# 4-20mA-generator.net
KiCad netlist of a schematic drawn in EAGLE
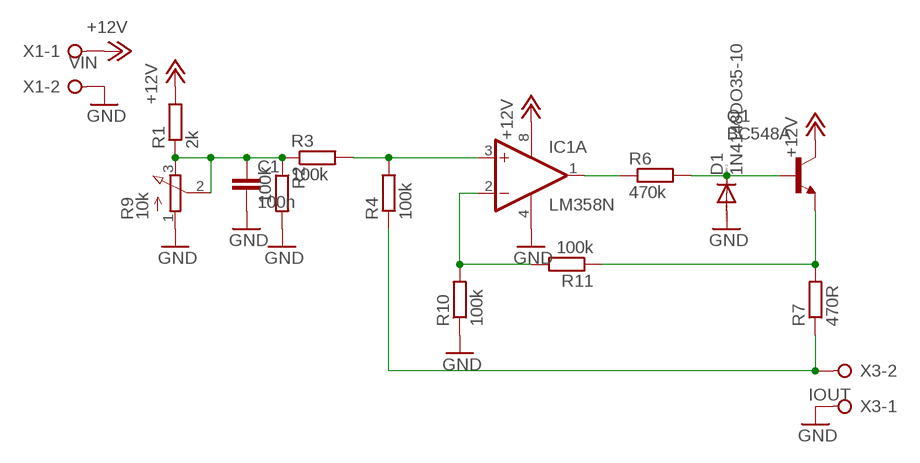
[diagram p0: schematic, sheet 1]

(export (version "E")
  (design (tool "Eeschema 10.0.6"))
  (components
    (comp (ref "C1")
      (value "100n")
      (footprint "eagle-import:C050-024X044")
      (libsource (lib "eagle-import") (part "C-EU050-024X044"))
    )
    (comp (ref "D1")
      (value "1N4148DO35-10")
      (footprint "eagle-import:DO35-10")
      (libsource (lib "eagle-import") (part "1N4148DO35-10"))
    )
    (comp (ref "IC1")
      (value "LM358N")
      (footprint "eagle-import:DIL08")
      (libsource (lib "eagle-import") (part "LM358N"))
    )
    (comp (ref "Q1")
      (value "BC548A")
      (footprint "eagle-import:TO92-EBC")
      (libsource (lib "eagle-import") (part "BC548A"))
    )
    (comp (ref "R1")
      (value "2k")
      (footprint "eagle-import:0207_7")
      (libsource (lib "eagle-import") (part "R-EU_0207/7"))
    )
    (comp (ref "R2")
      (value "100k")
      (footprint "eagle-import:0207_7")
      (libsource (lib "eagle-import") (part "R-EU_0207/7"))
    )
    (comp (ref "R3")
      (value "100k")
      (footprint "eagle-import:0207_7")
      (libsource (lib "eagle-import") (part "R-EU_0207/7"))
    )
    (comp (ref "R4")
      (value "100k")
      (footprint "eagle-import:0207_7")
      (libsource (lib "eagle-import") (part "R-EU_0207/7"))
    )
    (comp (ref "R6")
      (value "470k")
      (footprint "eagle-import:0207_7")
      (libsource (lib "eagle-import") (part "R-EU_0207/7"))
    )
    (comp (ref "R7")
      (value "470R")
      (footprint "eagle-import:0207_7")
      (libsource (lib "eagle-import") (part "R-EU_0207/7"))
    )
    (comp (ref "R9")
      (value "10k")
      (footprint "eagle-import:3RP_1610N")
      (libsource (lib "eagle-import") (part "3RP/1610N"))
    )
    (comp (ref "R10")
      (value "100k")
      (footprint "eagle-import:0207_7")
      (libsource (lib "eagle-import") (part "R-EU_0207/7"))
    )
    (comp (ref "R11")
      (value "100k")
      (footprint "eagle-import:0207_7")
      (libsource (lib "eagle-import") (part "R-EU_0207/7"))
    )
    (comp (ref "X1")
      (value "VIN")
      (footprint "eagle-import:W237-132")
      (libsource (lib "eagle-import") (part "W237-02P"))
    )
    (comp (ref "X3")
      (value "IOUT")
      (footprint "eagle-import:W237-132")
      (libsource (lib "eagle-import") (part "W237-02P"))
    )
  )
  (nets
    (net (code "1") (name "+12V") (class "Default")
      (node (ref "IC1") (pin "8") (pinfunction "V+_8") (pintype "power_in"))
      (node (ref "Q1") (pin "C") (pinfunction "C_C") (pintype "passive"))
      (node (ref "R1") (pin "2") (pinfunction "2_2") (pintype "passive"))
      (node (ref "X1") (pin "1") (pinfunction "KL_1") (pintype "passive"))
    )
    (net (code "2") (name "GND") (class "Default")
      (node (ref "C1") (pin "2") (pinfunction "2_2") (pintype "passive"))
      (node (ref "D1") (pin "A") (pinfunction "A_A") (pintype "passive"))
      (node (ref "IC1") (pin "4") (pinfunction "V-_4") (pintype "power_in"))
      (node (ref "R10") (pin "1") (pinfunction "1_1") (pintype "passive"))
      (node (ref "R2") (pin "2") (pinfunction "2_2") (pintype "passive"))
      (node (ref "R9") (pin "1") (pinfunction "A_1") (pintype "passive"))
      (node (ref "X1") (pin "2") (pinfunction "KL_2") (pintype "passive"))
      (node (ref "X3") (pin "1") (pinfunction "KL_1") (pintype "passive"))
    )
    (net (code "3") (name "Net-(D1-PadC)") (class "Default")
      (node (ref "D1") (pin "C") (pinfunction "C_C") (pintype "passive"))
      (node (ref "Q1") (pin "B") (pinfunction "B_B") (pintype "passive"))
      (node (ref "R6") (pin "2") (pinfunction "2_2") (pintype "passive"))
    )
    (net (code "4") (name "Net-(IC1A-+IN)") (class "Default")
      (node (ref "IC1") (pin "3") (pinfunction "+IN_3") (pintype "input"))
      (node (ref "R3") (pin "2") (pinfunction "2_2") (pintype "passive"))
      (node (ref "R4") (pin "2") (pinfunction "2_2") (pintype "passive"))
    )
    (net (code "5") (name "Net-(IC1A--IN)") (class "Default")
      (node (ref "IC1") (pin "2") (pinfunction "-IN_2") (pintype "input"))
      (node (ref "R10") (pin "2") (pinfunction "2_2") (pintype "passive"))
      (node (ref "R11") (pin "2") (pinfunction "2_2") (pintype "passive"))
    )
    (net (code "6") (name "Net-(IC1A-OUT)") (class "Default")
      (node (ref "IC1") (pin "1") (pinfunction "OUT_1") (pintype "output"))
      (node (ref "R6") (pin "1") (pinfunction "1_1") (pintype "passive"))
    )
    (net (code "7") (name "Net-(Q1-PadE)") (class "Default")
      (node (ref "Q1") (pin "E") (pinfunction "E_E") (pintype "passive"))
      (node (ref "R11") (pin "1") (pinfunction "1_1") (pintype "passive"))
      (node (ref "R7") (pin "2") (pinfunction "2_2") (pintype "passive"))
    )
    (net (code "8") (name "Net-(R9-E)") (class "Default")
      (node (ref "C1") (pin "1") (pinfunction "1_1") (pintype "passive"))
      (node (ref "R1") (pin "1") (pinfunction "1_1") (pintype "passive"))
      (node (ref "R2") (pin "1") (pinfunction "1_1") (pintype "passive"))
      (node (ref "R3") (pin "1") (pinfunction "1_1") (pintype "passive"))
      (node (ref "R9") (pin "2") (pinfunction "S_2") (pintype "passive"))
      (node (ref "R9") (pin "3") (pinfunction "E_3") (pintype "passive"))
    )
    (net (code "9") (name "Net-(X3B-KL)") (class "Default")
      (node (ref "R4") (pin "1") (pinfunction "1_1") (pintype "passive"))
      (node (ref "R7") (pin "1") (pinfunction "1_1") (pintype "passive"))
      (node (ref "X3") (pin "2") (pinfunction "KL_2") (pintype "passive"))
    )
  )
)
